# Ground_Station_Electronics.net
KiCad netlist of a schematic drawn in EasyEDA
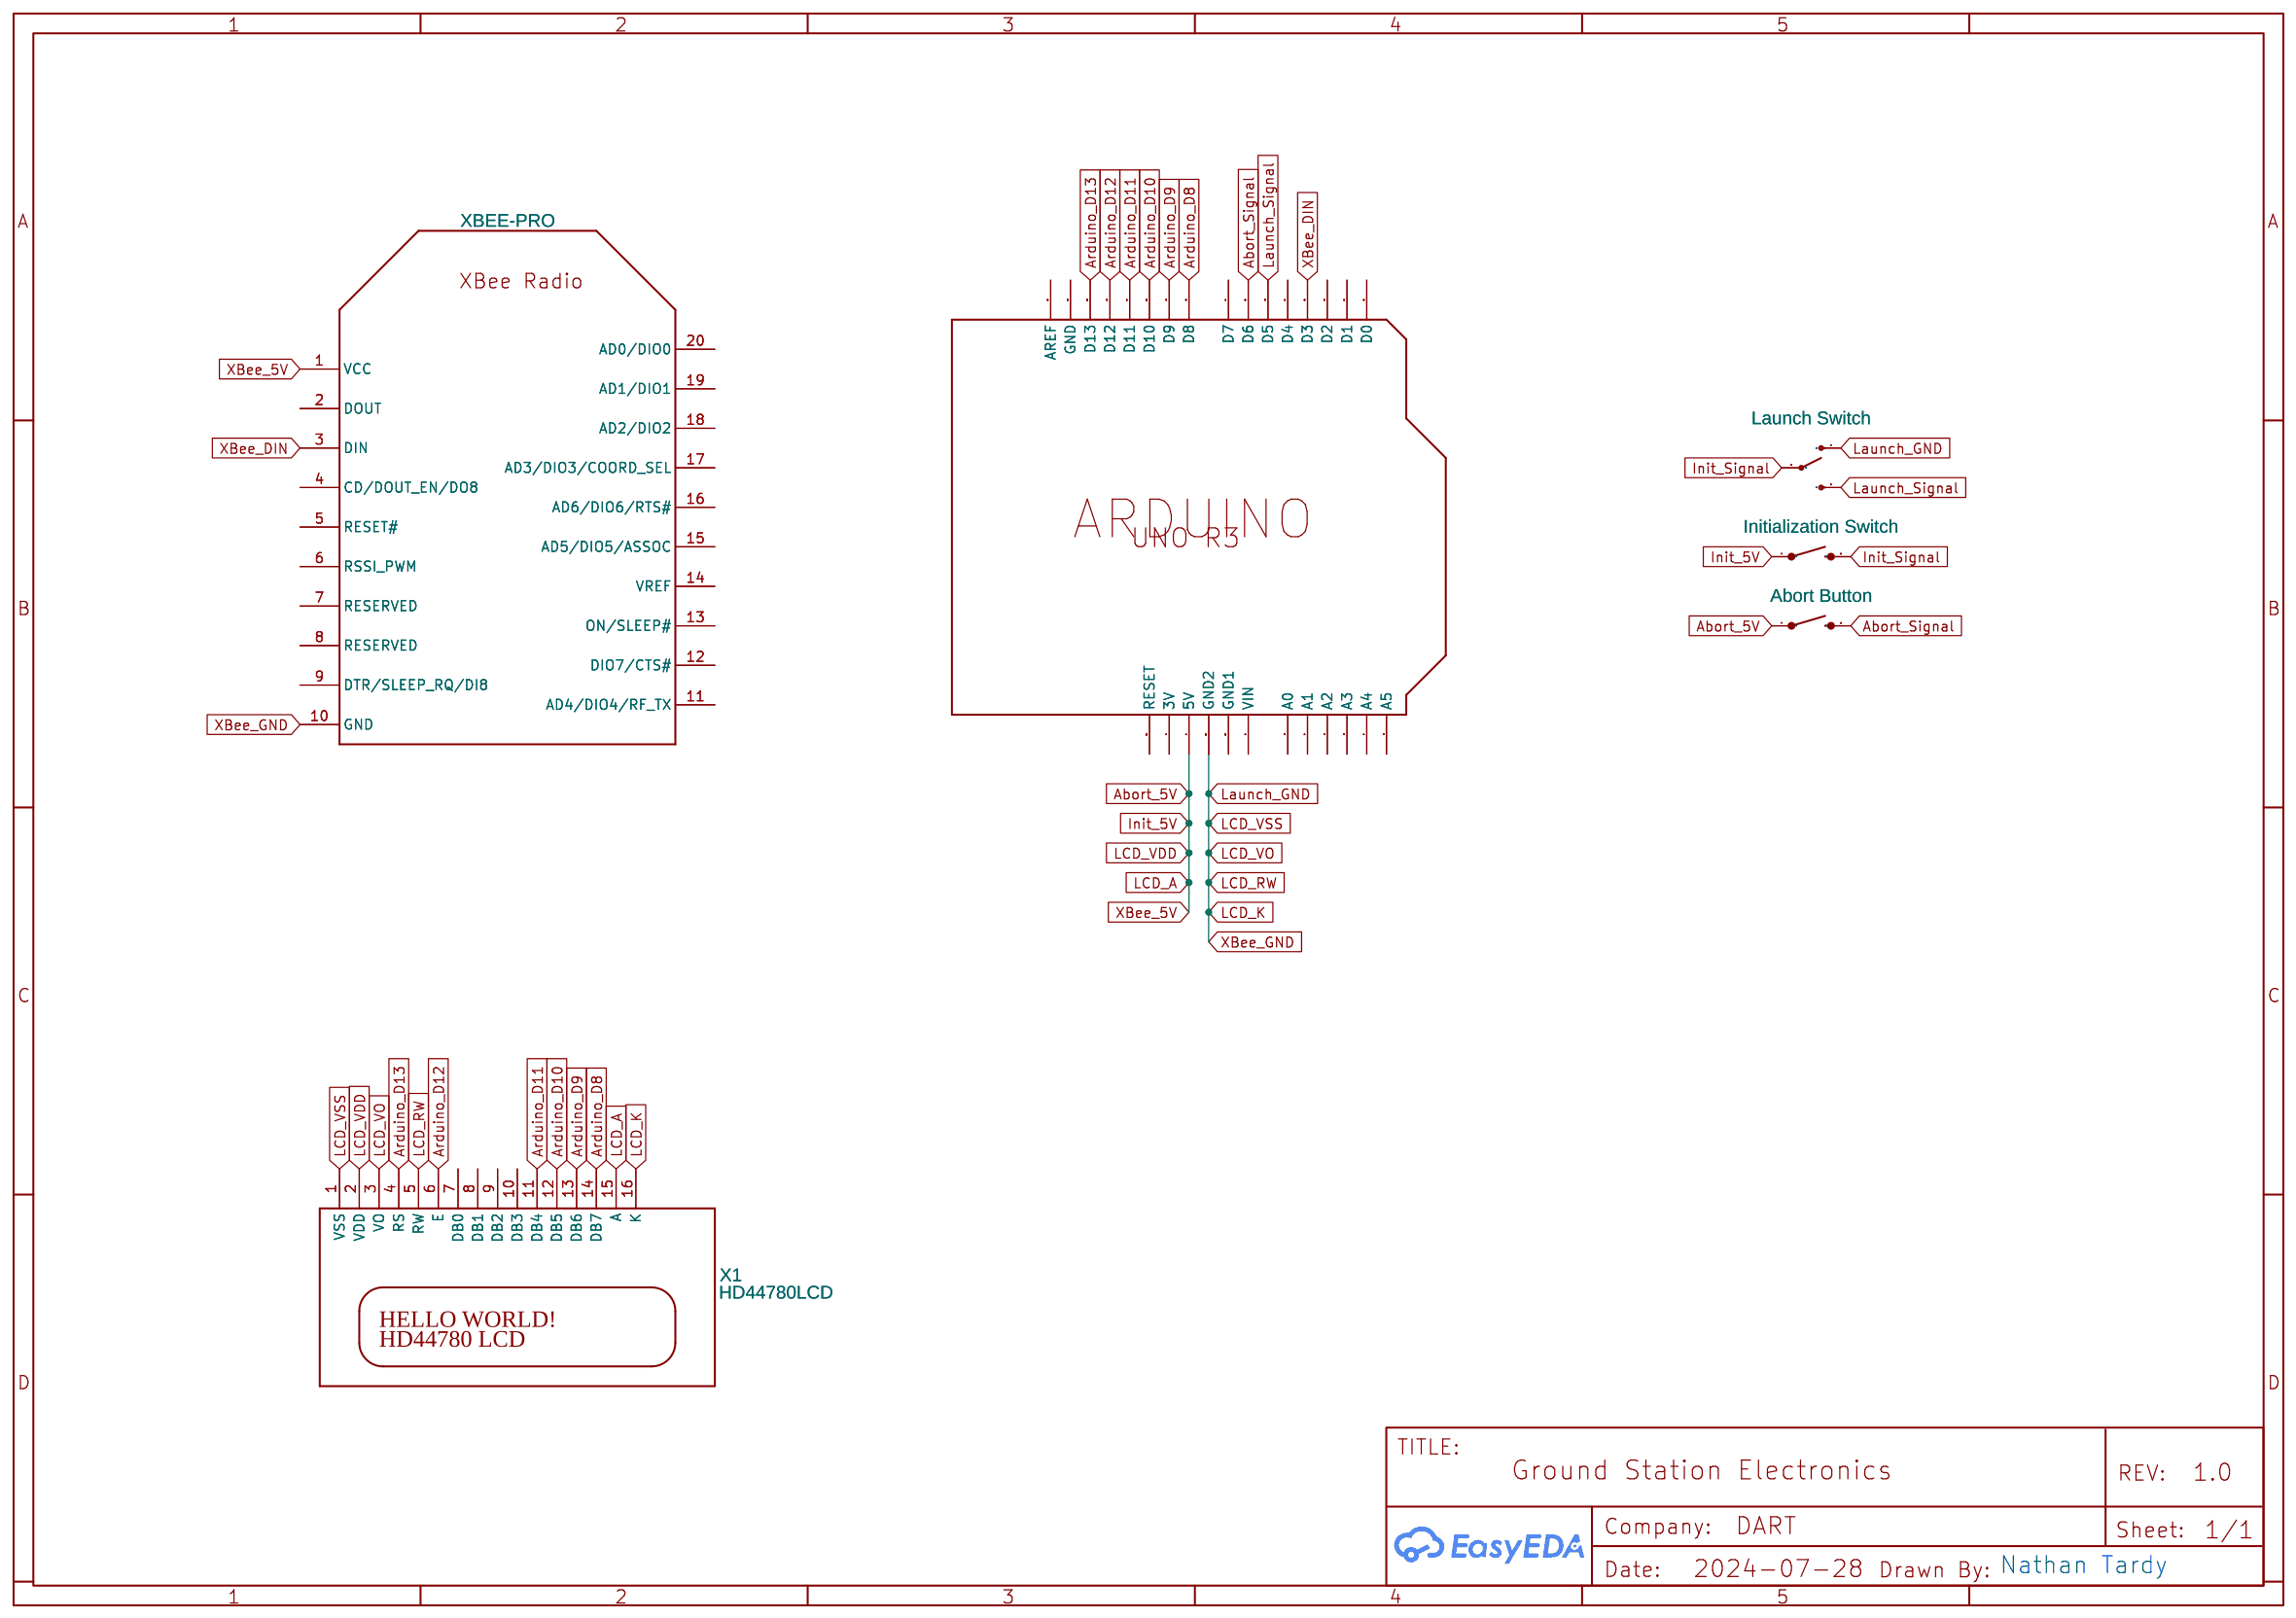
[diagram p0: schematic sheet]

(export (version "E")
  (design (tool "Eeschema 10.0.6"))
  (components
    (comp (ref "M1") (value "XBEE-PRO") (libsource (lib "") (part "XBEE-PRO")))
    (comp (ref "S1") (value "Initialization Switch") (libsource (lib "") (part "SWITCH-MOMENTARY-2SMD")))
    (comp (ref "S2") (value "Launch Switch") (libsource (lib "") (part "SWITCH-SPSTPTH2")))
    (comp (ref "S3") (value "Abort Button") (libsource (lib "") (part "SWITCH-MOMENTARY-2SMD")))
    (comp (ref "U2") (value "ARDUINOUNO") (libsource (lib "") (part "ARDUINOUNO")))
    (comp (ref "X1") (value "HD44780LCD") (libsource (lib "") (part "HD44780LCD")))
  )
  (nets
    (net (code "1") (name "Abort_5V") (class "Default")
      (node (ref "M1") (pin "1") (pinfunction "VCC_1") (pintype "bidirectional"))
      (node (ref "S1") (pin "1") (pinfunction "1_1") (pintype "unspecified"))
      (node (ref "S3") (pin "1") (pinfunction "1_1") (pintype "unspecified"))
      (node (ref "U2") (pin "5V") (pinfunction "5V_5V") (pintype "passive"))
      (node (ref "X1") (pin "15") (pinfunction "A_15") (pintype "input"))
      (node (ref "X1") (pin "2") (pinfunction "VDD_2") (pintype "unspecified"))
    )
    (net (code "2") (name "Abort_Signal") (class "Default")
      (node (ref "S3") (pin "3") (pinfunction "2_3") (pintype "unspecified"))
      (node (ref "U2") (pin "D6") (pinfunction "D6_D6") (pintype "unspecified"))
    )
    (net (code "3") (name "Arduino_D8") (class "Default")
      (node (ref "U2") (pin "D8") (pinfunction "D8_D8") (pintype "unspecified"))
      (node (ref "X1") (pin "14") (pinfunction "DB7_14") (pintype "unspecified"))
    )
    (net (code "4") (name "Arduino_D9") (class "Default")
      (node (ref "U2") (pin "D9") (pinfunction "D9_D9") (pintype "unspecified"))
      (node (ref "X1") (pin "13") (pinfunction "DB6_13") (pintype "unspecified"))
    )
    (net (code "5") (name "Arduino_D10") (class "Default")
      (node (ref "U2") (pin "D10") (pinfunction "D10_D10") (pintype "unspecified"))
      (node (ref "X1") (pin "12") (pinfunction "DB5_12") (pintype "unspecified"))
    )
    (net (code "6") (name "Arduino_D11") (class "Default")
      (node (ref "U2") (pin "D11") (pinfunction "D11_D11") (pintype "unspecified"))
      (node (ref "X1") (pin "11") (pinfunction "DB4_11") (pintype "unspecified"))
    )
    (net (code "7") (name "Arduino_D12") (class "Default")
      (node (ref "U2") (pin "D12") (pinfunction "D12_D12") (pintype "unspecified"))
      (node (ref "X1") (pin "6") (pinfunction "E_6") (pintype "input"))
    )
    (net (code "8") (name "Arduino_D13") (class "Default")
      (node (ref "U2") (pin "D13") (pinfunction "D13_D13") (pintype "unspecified"))
      (node (ref "X1") (pin "4") (pinfunction "RS_4") (pintype "input"))
    )
    (net (code "9") (name "Init_Signal") (class "Default")
      (node (ref "S1") (pin "3") (pinfunction "2_3") (pintype "unspecified"))
      (node (ref "S2") (pin "2") (pinfunction "P_2") (pintype "unspecified"))
    )
    (net (code "10") (name "LCD_K") (class "Default")
      (node (ref "M1") (pin "10") (pinfunction "GND_10") (pintype "bidirectional"))
      (node (ref "S2") (pin "1") (pinfunction "O_1") (pintype "unspecified"))
      (node (ref "U2") (pin "GND2") (pinfunction "GND2_GND2") (pintype "passive"))
      (node (ref "X1") (pin "1") (pinfunction "VSS_1") (pintype "unspecified"))
      (node (ref "X1") (pin "16") (pinfunction "K_16") (pintype "input"))
      (node (ref "X1") (pin "3") (pinfunction "VO_3") (pintype "input"))
      (node (ref "X1") (pin "5") (pinfunction "RW_5") (pintype "input"))
    )
    (net (code "11") (name "Launch_Signal") (class "Default")
      (node (ref "S2") (pin "3") (pinfunction "S_3") (pintype "unspecified"))
      (node (ref "U2") (pin "D5") (pinfunction "D5_D5") (pintype "unspecified"))
    )
    (net (code "12") (name "XBee_DIN") (class "Default")
      (node (ref "M1") (pin "3") (pinfunction "DIN_3") (pintype "bidirectional"))
      (node (ref "U2") (pin "D3") (pinfunction "D3_D3") (pintype "unspecified"))
    )
    (net (code "13") (name "unconnected-(M1-AD0{slash}DIO0-Pad20)") (class "Default")
      (node (ref "M1") (pin "20") (pinfunction "AD0/DIO0_20") (pintype "bidirectional"))
    )
    (net (code "14") (name "unconnected-(M1-AD1{slash}DIO1-Pad19)") (class "Default")
      (node (ref "M1") (pin "19") (pinfunction "AD1/DIO1_19") (pintype "bidirectional"))
    )
    (net (code "15") (name "unconnected-(M1-AD2{slash}DIO2-Pad18)") (class "Default")
      (node (ref "M1") (pin "18") (pinfunction "AD2/DIO2_18") (pintype "bidirectional"))
    )
    (net (code "16") (name "unconnected-(M1-AD3{slash}DIO3{slash}COORD_SEL-Pad17)") (class "Default")
      (node (ref "M1") (pin "17") (pinfunction "AD3/DIO3/COORD_SEL_17") (pintype "bidirectional"))
    )
    (net (code "17") (name "unconnected-(M1-AD4{slash}DIO4{slash}RF_TX-Pad11)") (class "Default")
      (node (ref "M1") (pin "11") (pinfunction "AD4/DIO4/RF_TX_11") (pintype "bidirectional"))
    )
    (net (code "18") (name "unconnected-(M1-AD5{slash}DIO5{slash}ASSOC-Pad15)") (class "Default")
      (node (ref "M1") (pin "15") (pinfunction "AD5/DIO5/ASSOC_15") (pintype "bidirectional"))
    )
    (net (code "19") (name "unconnected-(M1-AD6{slash}DIO6{slash}RTS#-Pad16)") (class "Default")
      (node (ref "M1") (pin "16") (pinfunction "AD6/DIO6/RTS#_16") (pintype "bidirectional"))
    )
    (net (code "20") (name "unconnected-(M1-CD{slash}DOUT_EN{slash}DO8-Pad4)") (class "Default")
      (node (ref "M1") (pin "4") (pinfunction "CD/DOUT_EN/DO8_4") (pintype "bidirectional"))
    )
    (net (code "21") (name "unconnected-(M1-DIO7{slash}CTS#-Pad12)") (class "Default")
      (node (ref "M1") (pin "12") (pinfunction "DIO7/CTS#_12") (pintype "bidirectional"))
    )
    (net (code "22") (name "unconnected-(M1-DOUT-Pad2)") (class "Default")
      (node (ref "M1") (pin "2") (pinfunction "DOUT_2") (pintype "bidirectional"))
    )
    (net (code "23") (name "unconnected-(M1-DTR{slash}SLEEP_RQ{slash}DI8-Pad9)") (class "Default")
      (node (ref "M1") (pin "9") (pinfunction "DTR/SLEEP_RQ/DI8_9") (pintype "bidirectional"))
    )
    (net (code "24") (name "unconnected-(M1-ON{slash}SLEEP#-Pad13)") (class "Default")
      (node (ref "M1") (pin "13") (pinfunction "ON/SLEEP#_13") (pintype "bidirectional"))
    )
    (net (code "25") (name "unconnected-(M1-RESERVED-Pad7)") (class "Default")
      (node (ref "M1") (pin "7") (pinfunction "RESERVED_7") (pintype "bidirectional"))
    )
    (net (code "26") (name "unconnected-(M1-RESERVED-Pad8)") (class "Default")
      (node (ref "M1") (pin "8") (pinfunction "RESERVED_8") (pintype "bidirectional"))
    )
    (net (code "27") (name "unconnected-(M1-RESET#-Pad5)") (class "Default")
      (node (ref "M1") (pin "5") (pinfunction "RESET#_5") (pintype "bidirectional"))
    )
    (net (code "28") (name "unconnected-(M1-RSSI_PWM-Pad6)") (class "Default")
      (node (ref "M1") (pin "6") (pinfunction "RSSI_PWM_6") (pintype "bidirectional"))
    )
    (net (code "29") (name "unconnected-(M1-VREF-Pad14)") (class "Default")
      (node (ref "M1") (pin "14") (pinfunction "VREF_14") (pintype "bidirectional"))
    )
    (net (code "30") (name "unconnected-(U2-Pad3V)") (class "Default")
      (node (ref "U2") (pin "3V") (pinfunction "3V_3V") (pintype "passive"))
    )
    (net (code "31") (name "unconnected-(U2-PadA0)") (class "Default")
      (node (ref "U2") (pin "A0") (pinfunction "A0_A0") (pintype "unspecified"))
    )
    (net (code "32") (name "unconnected-(U2-PadA1)") (class "Default")
      (node (ref "U2") (pin "A1") (pinfunction "A1_A1") (pintype "unspecified"))
    )
    (net (code "33") (name "unconnected-(U2-PadA2)") (class "Default")
      (node (ref "U2") (pin "A2") (pinfunction "A2_A2") (pintype "unspecified"))
    )
    (net (code "34") (name "unconnected-(U2-PadA3)") (class "Default")
      (node (ref "U2") (pin "A3") (pinfunction "A3_A3") (pintype "unspecified"))
    )
    (net (code "35") (name "unconnected-(U2-PadA4)") (class "Default")
      (node (ref "U2") (pin "A4") (pinfunction "A4_A4") (pintype "unspecified"))
    )
    (net (code "36") (name "unconnected-(U2-PadA5)") (class "Default")
      (node (ref "U2") (pin "A5") (pinfunction "A5_A5") (pintype "unspecified"))
    )
    (net (code "37") (name "unconnected-(U2-PadAREF)") (class "Default")
      (node (ref "U2") (pin "AREF") (pinfunction "AREF_AREF") (pintype "unspecified"))
    )
    (net (code "38") (name "unconnected-(U2-PadD0)") (class "Default")
      (node (ref "U2") (pin "D0") (pinfunction "D0_D0") (pintype "unspecified"))
    )
    (net (code "39") (name "unconnected-(U2-PadD1)") (class "Default")
      (node (ref "U2") (pin "D1") (pinfunction "D1_D1") (pintype "unspecified"))
    )
    (net (code "40") (name "unconnected-(U2-PadD2)") (class "Default")
      (node (ref "U2") (pin "D2") (pinfunction "D2_D2") (pintype "unspecified"))
    )
    (net (code "41") (name "unconnected-(U2-PadD4)") (class "Default")
      (node (ref "U2") (pin "D4") (pinfunction "D4_D4") (pintype "unspecified"))
    )
    (net (code "42") (name "unconnected-(U2-PadD7)") (class "Default")
      (node (ref "U2") (pin "D7") (pinfunction "D7_D7") (pintype "unspecified"))
    )
    (net (code "43") (name "unconnected-(U2-PadGND)") (class "Default")
      (node (ref "U2") (pin "GND") (pinfunction "GND_GND") (pintype "passive"))
    )
    (net (code "44") (name "unconnected-(U2-PadGND1)") (class "Default")
      (node (ref "U2") (pin "GND1") (pinfunction "GND1_GND1") (pintype "passive"))
    )
    (net (code "45") (name "unconnected-(U2-PadRESET)") (class "Default")
      (node (ref "U2") (pin "RESET") (pinfunction "RESET_RESET") (pintype "unspecified"))
    )
    (net (code "46") (name "unconnected-(U2-PadVIN)") (class "Default")
      (node (ref "U2") (pin "VIN") (pinfunction "VIN_VIN") (pintype "passive"))
    )
    (net (code "47") (name "unconnected-(X1-DB0-Pad7)") (class "Default")
      (node (ref "X1") (pin "7") (pinfunction "DB0_7") (pintype "unspecified"))
    )
    (net (code "48") (name "unconnected-(X1-DB1-Pad8)") (class "Default")
      (node (ref "X1") (pin "8") (pinfunction "DB1_8") (pintype "unspecified"))
    )
    (net (code "49") (name "unconnected-(X1-DB2-Pad9)") (class "Default")
      (node (ref "X1") (pin "9") (pinfunction "DB2_9") (pintype "unspecified"))
    )
    (net (code "50") (name "unconnected-(X1-DB3-Pad10)") (class "Default")
      (node (ref "X1") (pin "10") (pinfunction "DB3_10") (pintype "unspecified"))
    )
  )
)
